# InfraRed.net
KiCad netlist of a schematic drawn in Altium Designer
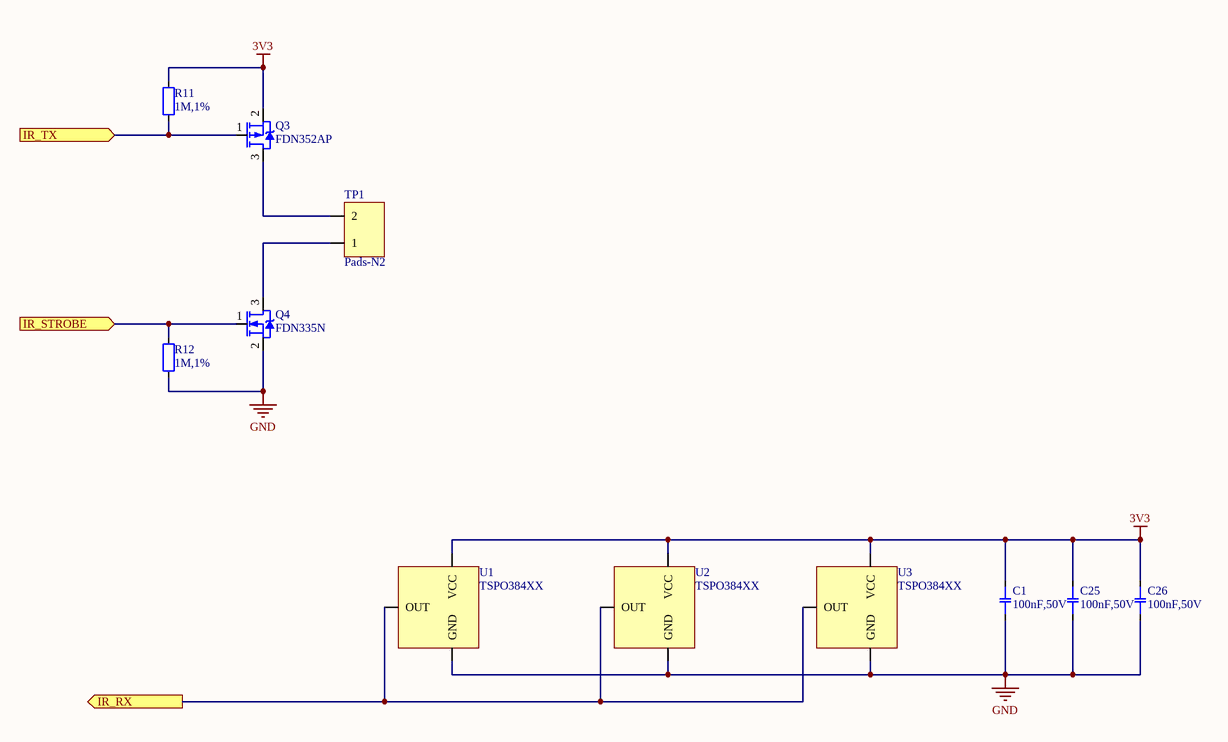
[diagram p0: InfraRed.SchDoc]

(export (version "E")
  (design (tool "Eeschema 10.0.6"))
  (components
    (comp (ref "C1")
      (value "100nF,50V")
      (footprint "CAPC1608X09N_0603")
      (description "CAP CER 0.1UF 50V 10% X7R 0603")
      (fields (field (name "MANUFACTURER") "Kemet") (field (name "TOLERANCE") "10%"))
      (libsource (lib "library") (part "CAP-NP_1"))
    )
    (comp (ref "C25")
      (value "100nF,50V")
      (footprint "CAPC1608X09N_0603")
      (description "CAP CER 0.1UF 50V 10% X7R 0603")
      (fields (field (name "MANUFACTURER") "Kemet") (field (name "TOLERANCE") "10%"))
      (libsource (lib "library") (part "CAP-NP_1"))
    )
    (comp (ref "C26")
      (value "100nF,50V")
      (footprint "CAPC1608X09N_0603")
      (description "CAP CER 0.1UF 50V 10% X7R 0603")
      (fields (field (name "MANUFACTURER") "Kemet") (field (name "TOLERANCE") "10%"))
      (libsource (lib "library") (part "CAP-NP_1"))
    )
    (comp (ref "Q3")
      (value "FDN352AP")
      (footprint "SOT95P230X110-3N_SOT23")
      (description "MOSFET P-CH 30V 1.3A SSOT-3")
      (fields (field (name "MANUFACTURER") "Fairchild"))
      (libsource (lib "library") (part "MOSFET-P_1"))
    )
    (comp (ref "Q4")
      (value "FDN335N")
      (footprint "SOT95P230X110-3N_SOT23")
      (description "MOSFET N-CH 20V 1.7A SSOT3")
      (fields (field (name "MANUFACTURER") "Fairchild Semiconductor"))
      (libsource (lib "library") (part "MOSFET-N_1"))
    )
    (comp (ref "R11")
      (value "1M,1%")
      (footprint "RESC1608X06N_0603")
      (description "RES 1.00M OHM 1/10W 1% 0603 SMD")
      (fields (field (name "MANUFACTURER") "Yageo") (field (name "POWER") "0.1W"))
      (libsource (lib "library") (part "RESISTOR_1"))
    )
    (comp (ref "R12")
      (value "1M,1%")
      (footprint "RESC1608X06N_0603")
      (description "RES 1.00M OHM 1/10W 1% 0603 SMD")
      (fields (field (name "MANUFACTURER") "Yageo") (field (name "POWER") "0.1W"))
      (libsource (lib "library") (part "RESISTOR_1"))
    )
    (comp (ref "TP1") (value "Pads-N2") (footprint "PADS-N2") (libsource (lib "Common") (part "Pads-N2")))
    (comp (ref "U1")
      (value "TSPO384XX")
      (footprint "VISHAY_TSOP_")
      (libsource (lib "Common") (part "TSPO384XX"))
    )
    (comp (ref "U2")
      (value "TSPO384XX")
      (footprint "VISHAY_TSOP_")
      (libsource (lib "Common") (part "TSPO384XX"))
    )
    (comp (ref "U3")
      (value "TSPO384XX")
      (footprint "VISHAY_TSOP_")
      (libsource (lib "Common") (part "TSPO384XX"))
    )
  )
  (nets
    (net (code "1") (name "/IR_RX") (class "Default")
      (node (ref "U1") (pin "1") (pinfunction "OUT_1") (pintype "passive"))
      (node (ref "U2") (pin "1") (pinfunction "OUT_1") (pintype "passive"))
      (node (ref "U3") (pin "1") (pinfunction "OUT_1") (pintype "passive"))
    )
    (net (code "2") (name "/IR_STROBE") (class "Default")
      (node (ref "Q4") (pin "1") (pinfunction "G_1") (pintype "passive"))
      (node (ref "R12") (pin "1") (pinfunction "1_1") (pintype "passive"))
    )
    (net (code "3") (name "/IR_TX") (class "Default")
      (node (ref "Q3") (pin "1") (pinfunction "G_1") (pintype "passive"))
      (node (ref "R11") (pin "2") (pinfunction "2_2") (pintype "passive"))
    )
    (net (code "4") (name "3V3") (class "Default")
      (node (ref "C1") (pin "1") (pinfunction "1_1") (pintype "passive"))
      (node (ref "C25") (pin "1") (pinfunction "1_1") (pintype "passive"))
      (node (ref "C26") (pin "1") (pinfunction "1_1") (pintype "passive"))
      (node (ref "Q3") (pin "2") (pinfunction "S_2") (pintype "passive"))
      (node (ref "R11") (pin "1") (pinfunction "1_1") (pintype "passive"))
      (node (ref "U1") (pin "3") (pinfunction "VCC_3") (pintype "passive"))
      (node (ref "U2") (pin "3") (pinfunction "VCC_3") (pintype "passive"))
      (node (ref "U3") (pin "3") (pinfunction "VCC_3") (pintype "passive"))
    )
    (net (code "5") (name "GND") (class "Default")
      (node (ref "C1") (pin "2") (pinfunction "2_2") (pintype "passive"))
      (node (ref "C25") (pin "2") (pinfunction "2_2") (pintype "passive"))
      (node (ref "C26") (pin "2") (pinfunction "2_2") (pintype "passive"))
      (node (ref "Q4") (pin "2") (pinfunction "S_2") (pintype "passive"))
      (node (ref "R12") (pin "2") (pinfunction "2_2") (pintype "passive"))
      (node (ref "U1") (pin "2") (pinfunction "GND_2") (pintype "passive"))
      (node (ref "U2") (pin "2") (pinfunction "GND_2") (pintype "passive"))
      (node (ref "U3") (pin "2") (pinfunction "GND_2") (pintype "passive"))
    )
    (net (code "6") (name "Net-(Q3-D)") (class "Default")
      (node (ref "Q3") (pin "3") (pinfunction "D_3") (pintype "passive"))
      (node (ref "TP1") (pin "2") (pinfunction "2_2") (pintype "passive"))
    )
    (net (code "7") (name "Net-(Q4-D)") (class "Default")
      (node (ref "Q4") (pin "3") (pinfunction "D_3") (pintype "passive"))
      (node (ref "TP1") (pin "1") (pinfunction "1_1") (pintype "passive"))
    )
  )
)
